# v1-psas-dev-board.net
KiCad netlist of a schematic drawn in EAGLE
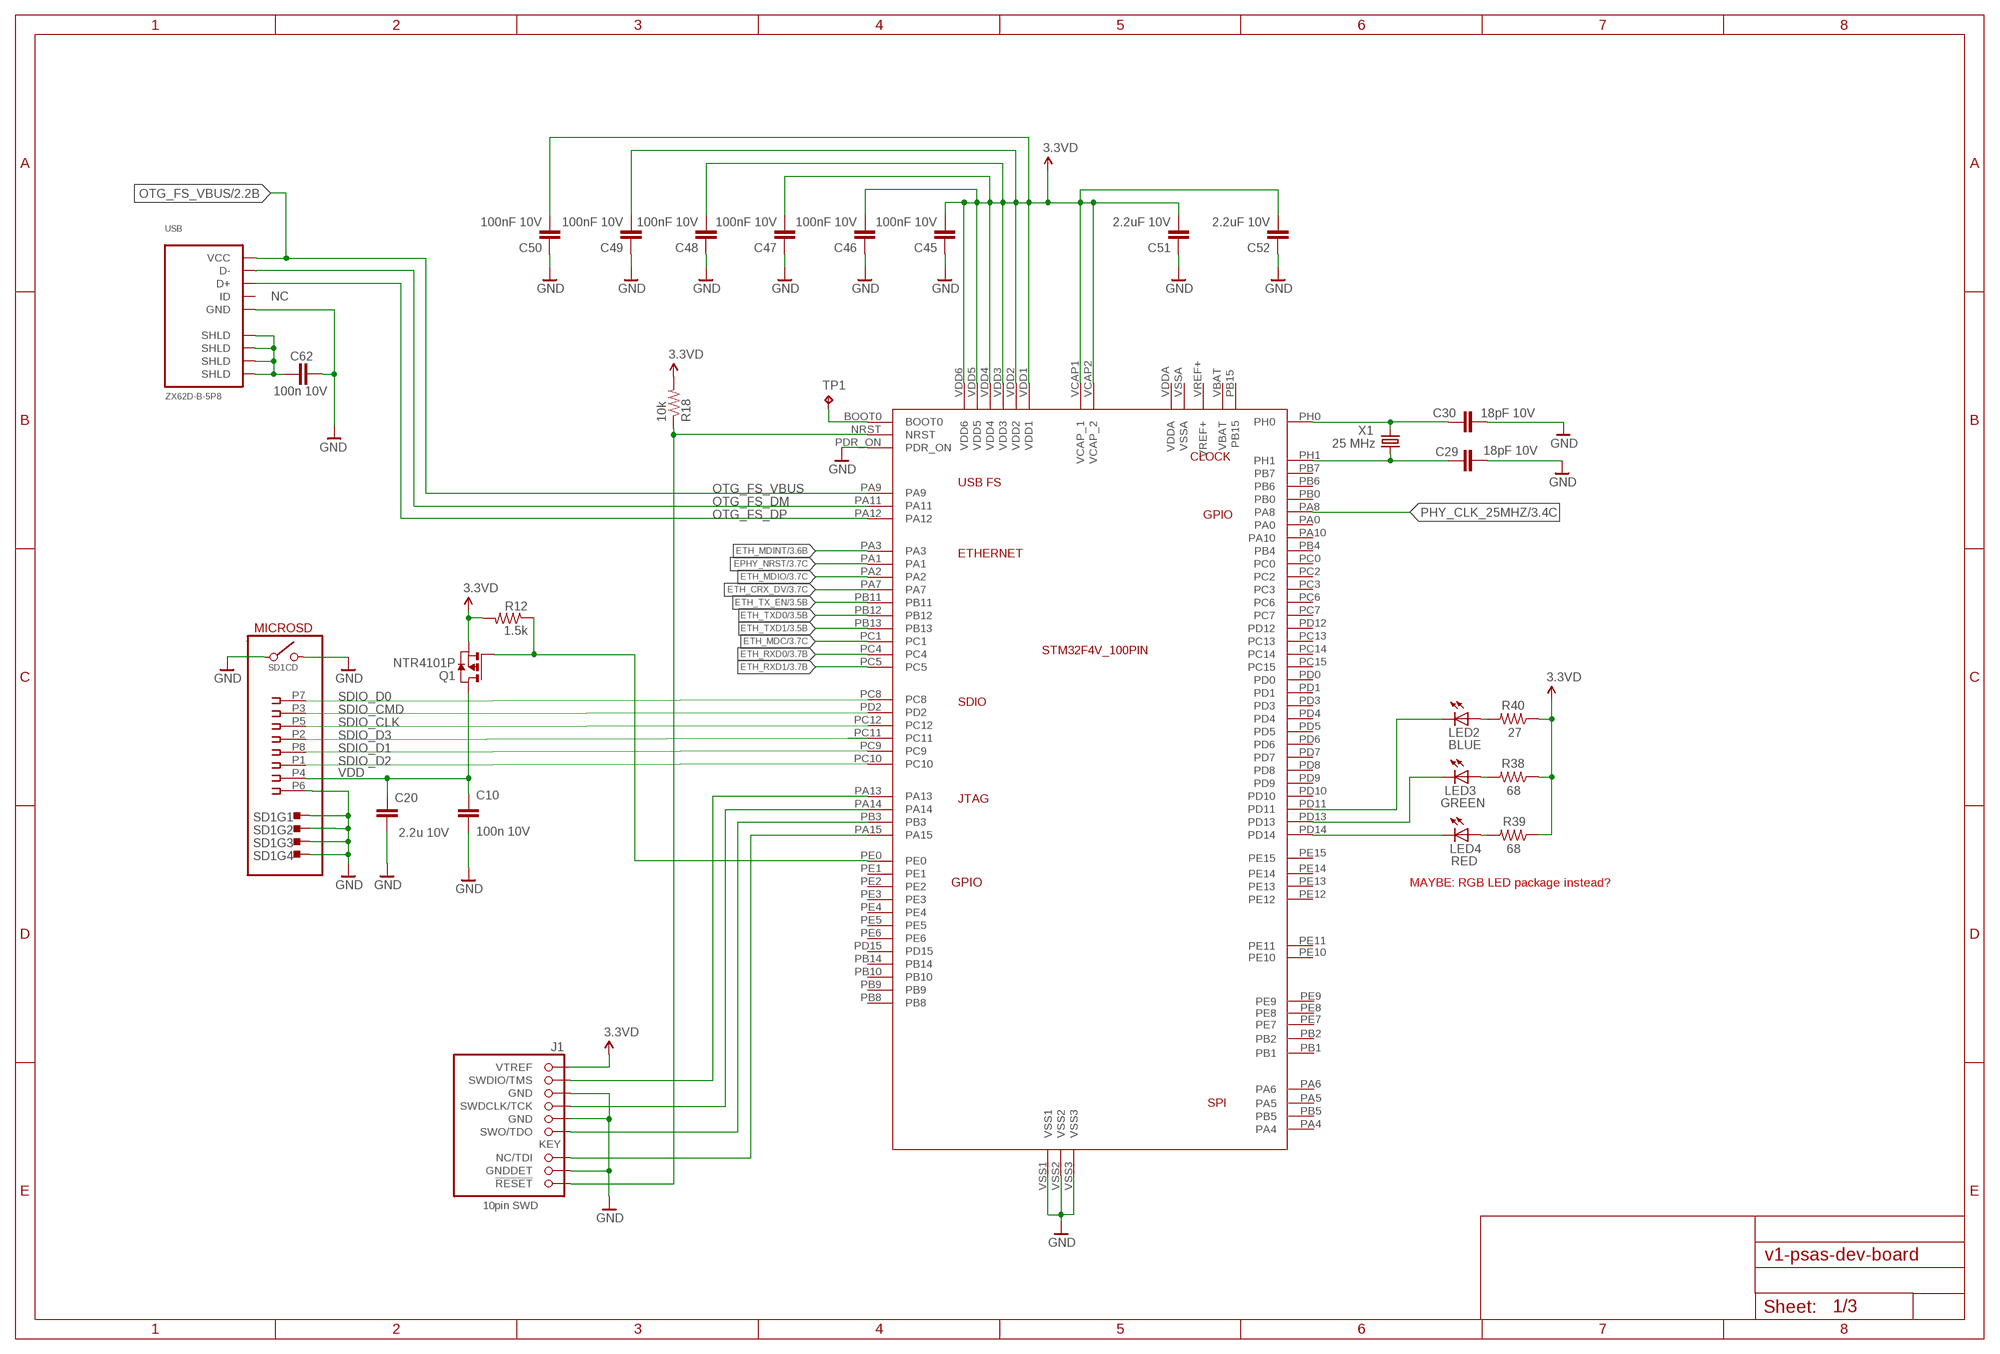
[diagram p0: schematic, sheet 1]
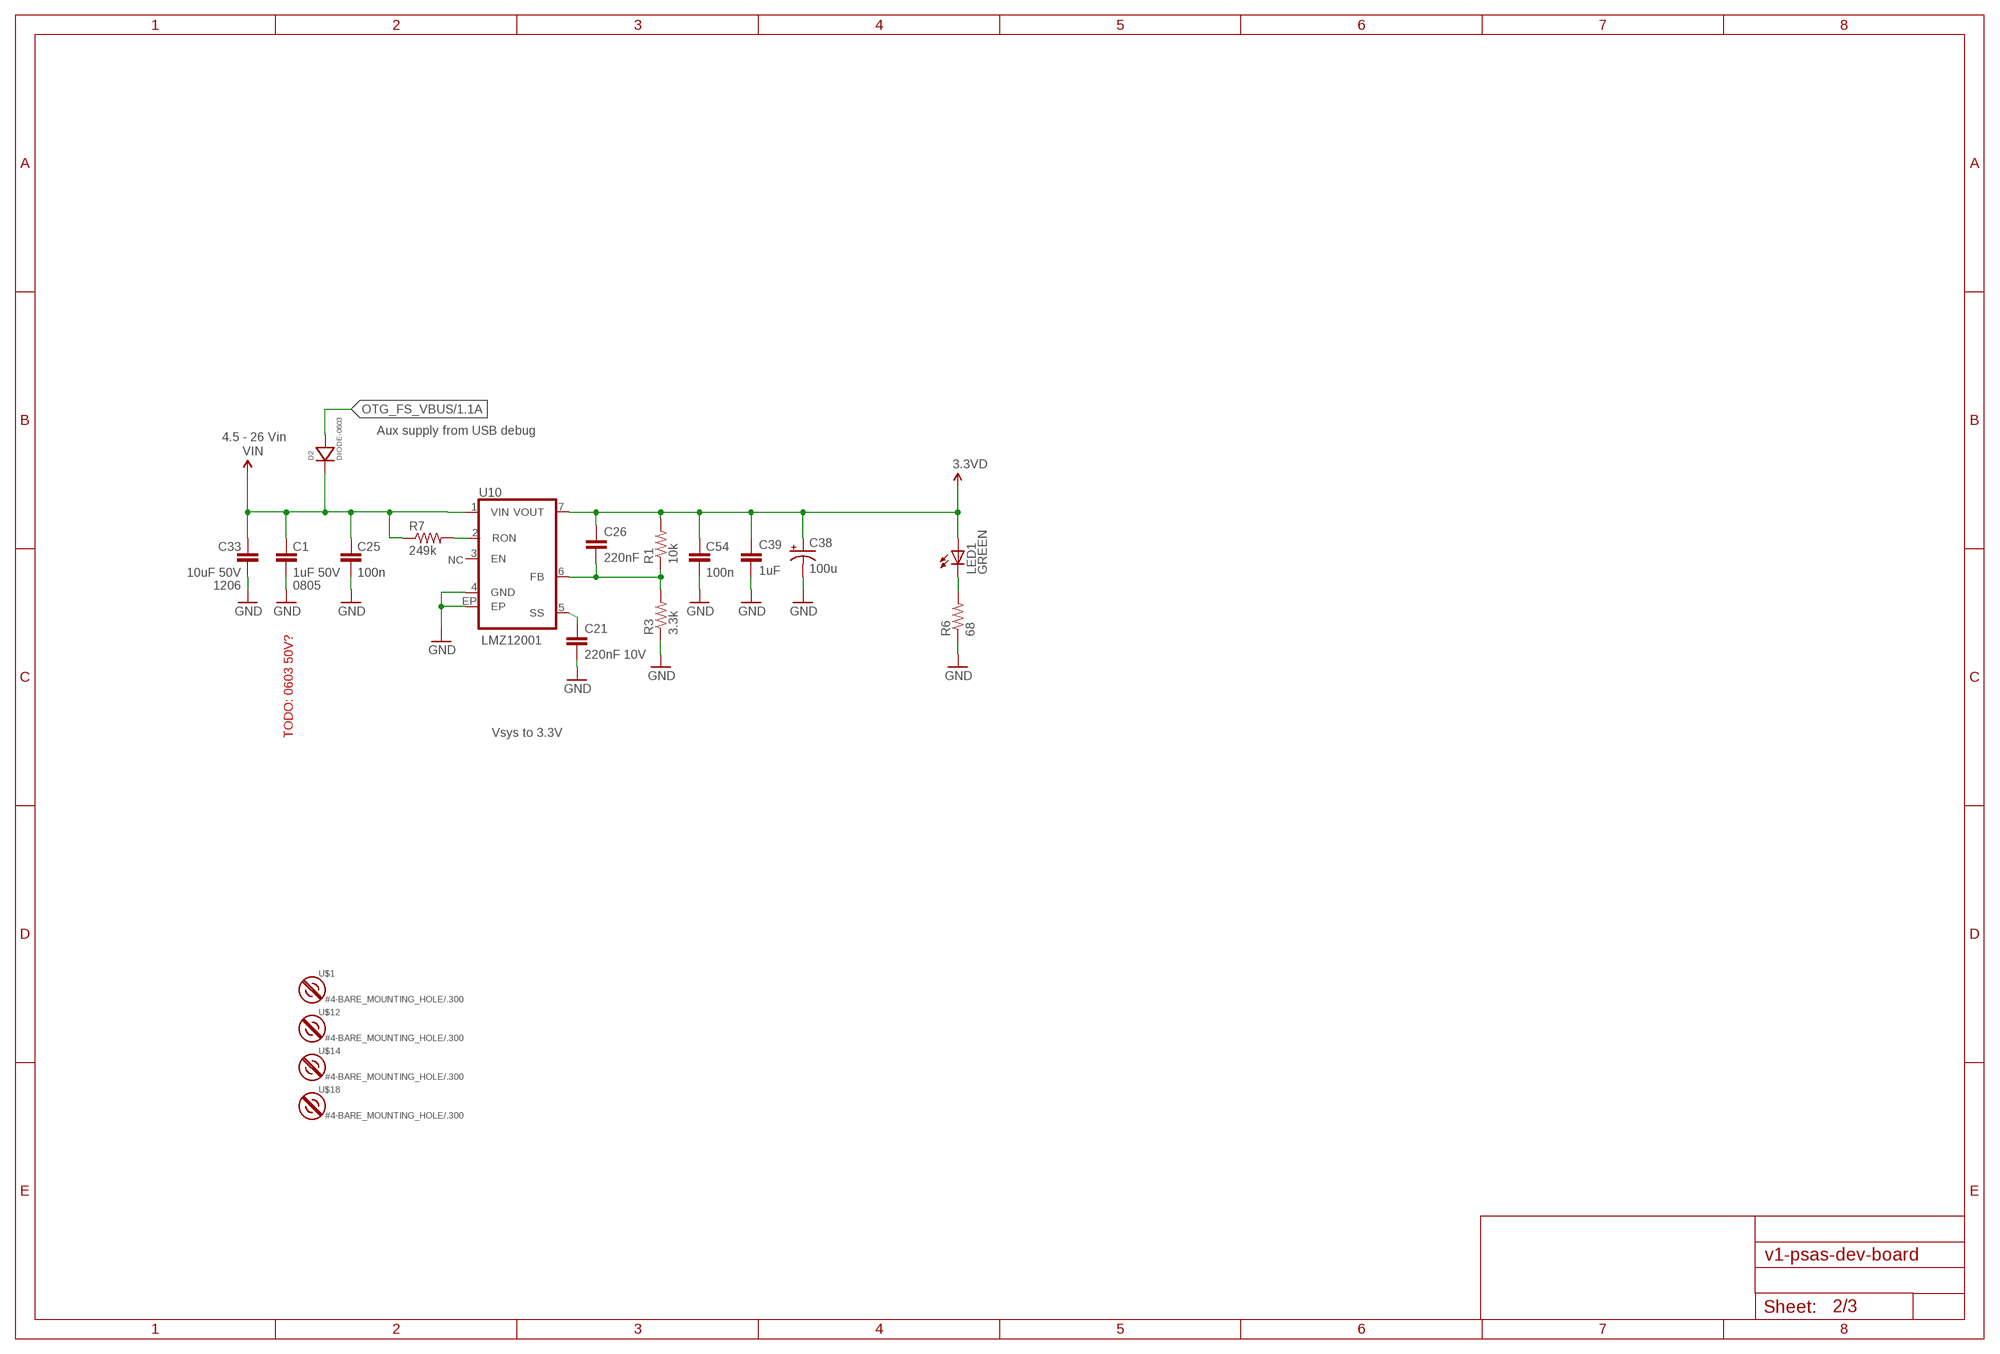
[diagram p1: schematic, sheet 2]
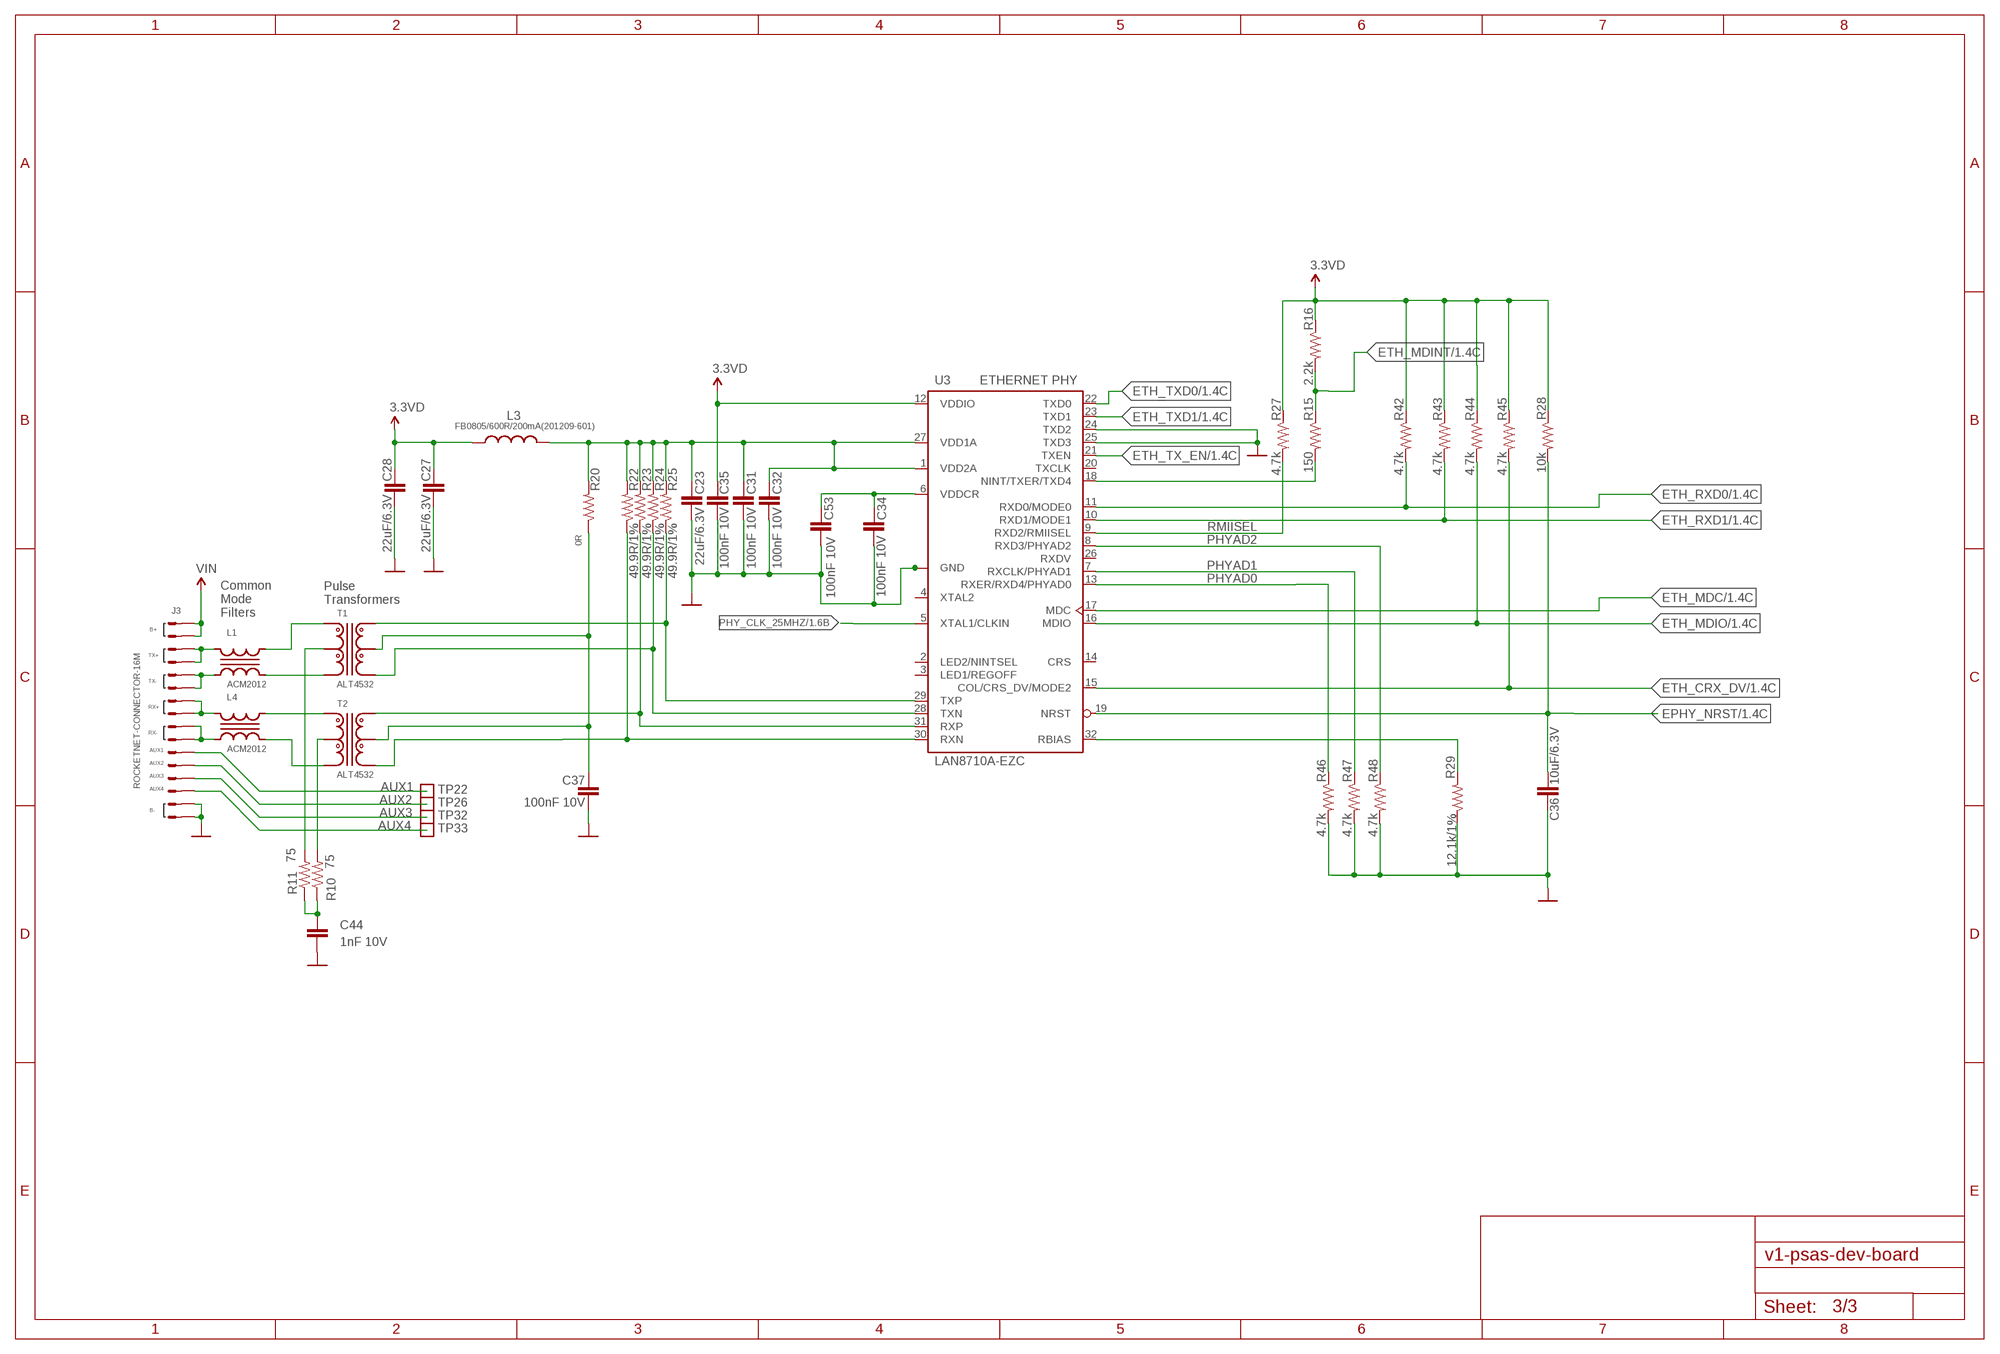
[diagram p2: schematic, sheet 3]

(export (version "E")
  (design (tool "Eeschema 10.0.6"))
  (components
    (comp (ref "C23")
      (value "22uF/6.3V")
      (footprint "eagle-import:1206-C")
      (libsource (lib "eagle-import") (part "C-EU1206-C"))
    )
    (comp (ref "C27")
      (value "22uF/6.3V")
      (footprint "eagle-import:1206-C")
      (libsource (lib "eagle-import") (part "C-EU1206-C"))
    )
    (comp (ref "C28")
      (value "22uF/6.3V")
      (footprint "eagle-import:1206-C")
      (libsource (lib "eagle-import") (part "C-EU1206-C"))
    )
    (comp (ref "C31")
      (value "100nF 10V")
      (footprint "eagle-import:0402-C-NOSILK")
      (libsource (lib "eagle-import") (part "C-EU0402-C-NOSILK"))
    )
    (comp (ref "C32")
      (value "100nF 10V")
      (footprint "eagle-import:0402-C-NOSILK")
      (libsource (lib "eagle-import") (part "C-EU0402-C-NOSILK"))
    )
    (comp (ref "C34")
      (value "100nF 10V")
      (footprint "eagle-import:0402-C-NOSILK")
      (libsource (lib "eagle-import") (part "C-EU0402-C-NOSILK"))
    )
    (comp (ref "C35")
      (value "100nF 10V")
      (footprint "eagle-import:0402-C-NOSILK")
      (libsource (lib "eagle-import") (part "C-EU0402-C-NOSILK"))
    )
    (comp (ref "C36")
      (value "10uF/6.3V")
      (footprint "eagle-import:1206-C")
      (libsource (lib "eagle-import") (part "C-EU1206-C"))
    )
    (comp (ref "C37")
      (value "100nF 10V")
      (footprint "eagle-import:0402-C-NOSILK")
      (libsource (lib "eagle-import") (part "C-EU0402-C-NOSILK"))
    )
    (comp (ref "C44")
      (value "1nF 10V")
      (footprint "eagle-import:0402-C-NOSILK")
      (libsource (lib "eagle-import") (part "C-EU0402-C-NOSILK"))
    )
    (comp (ref "C53")
      (value "100nF 10V")
      (footprint "eagle-import:0402-C-NOSILK")
      (libsource (lib "eagle-import") (part "C-EU0402-C-NOSILK"))
    )
    (comp (ref "J3")
      (value "ROCKETNET-CONNECTOR-16M")
      (footprint "eagle-import:ROCKETNET-M-16")
      (libsource (lib "eagle-import") (part "ROCKETNET-CONNECTOR-16M"))
    )
    (comp (ref "L1")
      (value "ACM2012")
      (footprint "eagle-import:TDK-ACM2012")
      (libsource (lib "eagle-import") (part "ACM2012"))
    )
    (comp (ref "L3")
      (value "FB0805/600R/200mA(201209-601)")
      (footprint "eagle-import:0805-C-NOSILK")
      (libsource (lib "eagle-import") (part "L-US0805-C-NOSILK"))
    )
    (comp (ref "L4")
      (value "ACM2012")
      (footprint "eagle-import:TDK-ACM2012")
      (libsource (lib "eagle-import") (part "ACM2012"))
    )
    (comp (ref "R10")
      (value "75")
      (footprint "eagle-import:0402-C-NOSILK")
      (libsource (lib "eagle-import") (part "R-US_0402-C-NOSILK"))
    )
    (comp (ref "R11")
      (value "75")
      (footprint "eagle-import:0402-C-NOSILK")
      (libsource (lib "eagle-import") (part "R-US_0402-C-NOSILK"))
    )
    (comp (ref "R15")
      (value "150")
      (footprint "eagle-import:0402-C-NOSILK")
      (libsource (lib "eagle-import") (part "R-US_0402-C-NOSILK"))
    )
    (comp (ref "R16")
      (value "2.2k")
      (footprint "eagle-import:0402-C-NOSILK")
      (libsource (lib "eagle-import") (part "R-US_0402-C-NOSILK"))
    )
    (comp (ref "R20")
      (value "0R")
      (footprint "eagle-import:0402-C-NOSILK")
      (libsource (lib "eagle-import") (part "R-US_0402-C-NOSILK"))
    )
    (comp (ref "R22")
      (value "49.9R/1%")
      (footprint "eagle-import:0402-C-NOSILK")
      (libsource (lib "eagle-import") (part "R-US_0402-C-NOSILK"))
    )
    (comp (ref "R23")
      (value "49.9R/1%")
      (footprint "eagle-import:0402-C-NOSILK")
      (libsource (lib "eagle-import") (part "R-US_0402-C-NOSILK"))
    )
    (comp (ref "R24")
      (value "49.9R/1%")
      (footprint "eagle-import:0402-C-NOSILK")
      (libsource (lib "eagle-import") (part "R-US_0402-C-NOSILK"))
    )
    (comp (ref "R25")
      (value "49.9R/1%")
      (footprint "eagle-import:0402-C-NOSILK")
      (libsource (lib "eagle-import") (part "R-US_0402-C-NOSILK"))
    )
    (comp (ref "R27")
      (value "4.7k")
      (footprint "eagle-import:0402-C-NOSILK")
      (libsource (lib "eagle-import") (part "R-US_0402-C-NOSILK"))
    )
    (comp (ref "R28")
      (value "10k")
      (footprint "eagle-import:0402-C-NOSILK")
      (libsource (lib "eagle-import") (part "R-US_0402-C-NOSILK"))
    )
    (comp (ref "R29")
      (value "12.1k/1%")
      (footprint "eagle-import:0402-C-NOSILK")
      (libsource (lib "eagle-import") (part "R-US_0402-C-NOSILK"))
    )
    (comp (ref "R42")
      (value "4.7k")
      (footprint "eagle-import:0402-C-NOSILK")
      (libsource (lib "eagle-import") (part "R-US_0402-C-NOSILK"))
    )
    (comp (ref "R43")
      (value "4.7k")
      (footprint "eagle-import:0402-C-NOSILK")
      (libsource (lib "eagle-import") (part "R-US_0402-C-NOSILK"))
    )
    (comp (ref "R44")
      (value "4.7k")
      (footprint "eagle-import:0402-C-NOSILK")
      (libsource (lib "eagle-import") (part "R-US_0402-C-NOSILK"))
    )
    (comp (ref "R45")
      (value "4.7k")
      (footprint "eagle-import:0402-C-NOSILK")
      (libsource (lib "eagle-import") (part "R-US_0402-C-NOSILK"))
    )
    (comp (ref "R46")
      (value "4.7k")
      (footprint "eagle-import:0402-C-NOSILK")
      (libsource (lib "eagle-import") (part "R-US_0402-C-NOSILK"))
    )
    (comp (ref "R47")
      (value "4.7k")
      (footprint "eagle-import:0402-C-NOSILK")
      (libsource (lib "eagle-import") (part "R-US_0402-C-NOSILK"))
    )
    (comp (ref "R48")
      (value "4.7k")
      (footprint "eagle-import:0402-C-NOSILK")
      (libsource (lib "eagle-import") (part "R-US_0402-C-NOSILK"))
    )
    (comp (ref "T1")
      (value "ALT4532")
      (footprint "eagle-import:TDK-ALT4532")
      (libsource (lib "eagle-import") (part "ALT4532"))
    )
    (comp (ref "T2")
      (value "ALT4532")
      (footprint "eagle-import:TDK-ALT4532")
      (libsource (lib "eagle-import") (part "ALT4532"))
    )
    (comp (ref "TP22")
      (value "TEST-POINT")
      (footprint "eagle-import:2MM-TEST-POINT")
      (libsource (lib "eagle-import") (part "TEST-POINT"))
    )
    (comp (ref "TP26")
      (value "TEST-POINT")
      (footprint "eagle-import:2MM-TEST-POINT")
      (libsource (lib "eagle-import") (part "TEST-POINT"))
    )
    (comp (ref "TP32")
      (value "TEST-POINT")
      (footprint "eagle-import:2MM-TEST-POINT")
      (libsource (lib "eagle-import") (part "TEST-POINT"))
    )
    (comp (ref "TP33")
      (value "TEST-POINT")
      (footprint "eagle-import:2MM-TEST-POINT")
      (libsource (lib "eagle-import") (part "TEST-POINT"))
    )
    (comp (ref "U3")
      (value "LAN8710A-EZC")
      (footprint "eagle-import:QFN-32(DRILLS)")
      (libsource (lib "eagle-import") (part "LAN8710A-EZC"))
    )
    (comp (ref "C10")
      (value "100n 10V")
      (footprint "eagle-import:0402-C-NOSILK")
      (libsource (lib "eagle-import") (part "C-EU0402-C-NOSILK"))
    )
    (comp (ref "C20")
      (value "2.2u 10V")
      (footprint "eagle-import:0603-C-NOSILK")
      (libsource (lib "eagle-import") (part "C-EU0603-C-NOSILK"))
    )
    (comp (ref "C29")
      (value "18pF 10V")
      (footprint "eagle-import:0402-C-NOSILK")
      (libsource (lib "eagle-import") (part "C-EU0402-C-NOSILK"))
    )
    (comp (ref "C30")
      (value "18pF 10V")
      (footprint "eagle-import:0402-C-NOSILK")
      (libsource (lib "eagle-import") (part "C-EU0402-C-NOSILK"))
    )
    (comp (ref "C45")
      (value "100nF 10V")
      (footprint "eagle-import:0402-C-NOSILK")
      (libsource (lib "eagle-import") (part "C-EU0402-C-NOSILK"))
    )
    (comp (ref "C46")
      (value "100nF 10V")
      (footprint "eagle-import:0402-C-NOSILK")
      (libsource (lib "eagle-import") (part "C-EU0402-C-NOSILK"))
    )
    (comp (ref "C47")
      (value "100nF 10V")
      (footprint "eagle-import:0402-C-NOSILK")
      (libsource (lib "eagle-import") (part "C-EU0402-C-NOSILK"))
    )
    (comp (ref "C48")
      (value "100nF 10V")
      (footprint "eagle-import:0402-C-NOSILK")
      (libsource (lib "eagle-import") (part "C-EU0402-C-NOSILK"))
    )
    (comp (ref "C49")
      (value "100nF 10V")
      (footprint "eagle-import:0402-C-NOSILK")
      (libsource (lib "eagle-import") (part "C-EU0402-C-NOSILK"))
    )
    (comp (ref "C50")
      (value "100nF 10V")
      (footprint "eagle-import:0402-C-NOSILK")
      (libsource (lib "eagle-import") (part "C-EU0402-C-NOSILK"))
    )
    (comp (ref "C51")
      (value "2.2uF 10V")
      (footprint "eagle-import:0603-C-NOSILK")
      (libsource (lib "eagle-import") (part "C-EU0603-C-NOSILK"))
    )
    (comp (ref "C52")
      (value "2.2uF 10V")
      (footprint "eagle-import:0603-C-NOSILK")
      (libsource (lib "eagle-import") (part "C-EU0603-C-NOSILK"))
    )
    (comp (ref "C62")
      (value "100n 10V")
      (footprint "eagle-import:0402-C-NOSILK")
      (libsource (lib "eagle-import") (part "C-EU0402-C-NOSILK"))
    )
    (comp (ref "J1")
      (value "1.27MM-SWD-CONNECTOR")
      (footprint "eagle-import:1.27MM_2X5")
      (libsource (lib "eagle-import") (part "1.27MM-SWD-CONNECTOR"))
    )
    (comp (ref "LED2")
      (value "BLUE")
      (footprint "eagle-import:CHIP-LED0603")
      (libsource (lib "eagle-import") (part "LEDCHIP-LED0603"))
    )
    (comp (ref "LED3")
      (value "GREEN")
      (footprint "eagle-import:CHIP-LED0603")
      (libsource (lib "eagle-import") (part "LEDCHIP-LED0603"))
    )
    (comp (ref "LED4")
      (value "RED")
      (footprint "eagle-import:CHIP-LED0603")
      (libsource (lib "eagle-import") (part "LEDCHIP-LED0603"))
    )
    (comp (ref "Q1")
      (value "NTR4101P")
      (footprint "eagle-import:SOT23")
      (libsource (lib "eagle-import") (part "NTR4101P"))
    )
    (comp (ref "R12")
      (value "1.5k")
      (footprint "eagle-import:0402-C-NOSILK")
      (libsource (lib "eagle-import") (part "R-US_0402-C-NOSILK"))
    )
    (comp (ref "R18")
      (value "10k")
      (footprint "eagle-import:0402-C-NOSILK")
      (libsource (lib "eagle-import") (part "R-US_0402-C-NOSILK"))
    )
    (comp (ref "R38")
      (value "68")
      (footprint "eagle-import:0402-C-NOSILK")
      (libsource (lib "eagle-import") (part "R-US_0402-C-NOSILK"))
    )
    (comp (ref "R39")
      (value "68")
      (footprint "eagle-import:0402-C-NOSILK")
      (libsource (lib "eagle-import") (part "R-US_0402-C-NOSILK"))
    )
    (comp (ref "R40")
      (value "27")
      (footprint "eagle-import:0402-C-NOSILK")
      (libsource (lib "eagle-import") (part "R-US_0402-C-NOSILK"))
    )
    (comp (ref "SD1")
      (value "CON_HIROSE_DM3D(MICROSD)")
      (footprint "eagle-import:HIROSE_DM3D(MICRO-SD)")
      (libsource (lib "eagle-import") (part "CON_HIROSE_DM3D(MICROSD)"))
    )
    (comp (ref "TP1")
      (value "TPTP06R")
      (footprint "eagle-import:TP06R")
      (libsource (lib "eagle-import") (part "TPTP06R"))
    )
    (comp (ref "U8")
      (value "STM32F4V")
      (footprint "eagle-import:LQFP100")
      (libsource (lib "eagle-import") (part "STM32F4V_100PIN_GPSBOARD"))
    )
    (comp (ref "USB")
      (value "ZX62D-B-5P8")
      (footprint "eagle-import:ZX62D-B-5P8")
      (libsource (lib "eagle-import") (part "ZX62D-B-5P8"))
    )
    (comp (ref "X1")
      (value "25 MHz")
      (footprint "eagle-import:CTS406")
      (libsource (lib "eagle-import") (part "CRYSTALCTS406"))
    )
    (comp (ref "C1")
      (value "1uF 50V")
      (footprint "eagle-import:0805-B-NOSILK")
      (libsource (lib "eagle-import") (part "C-EU0805-B-NOSILK"))
    )
    (comp (ref "C21")
      (value "220nF 10V")
      (footprint "eagle-import:0402-C-NOSILK")
      (libsource (lib "eagle-import") (part "C-EU0402-C-NOSILK"))
    )
    (comp (ref "C25")
      (value "100n")
      (footprint "eagle-import:0402-B-NOSILK")
      (libsource (lib "eagle-import") (part "C-EU0402-B-NOSILK"))
    )
    (comp (ref "C26")
      (value "220nF")
      (footprint "eagle-import:0402-C-NOSILK")
      (libsource (lib "eagle-import") (part "C-EU0402-C-NOSILK"))
    )
    (comp (ref "C33")
      (value "10uF 50V")
      (footprint "eagle-import:1206-C")
      (libsource (lib "eagle-import") (part "C-EU1206-C"))
    )
    (comp (ref "C38")
      (value "100u")
      (footprint "eagle-import:EIA6032")
      (libsource (lib "eagle-import") (part "CAP_POL6032"))
    )
    (comp (ref "C39")
      (value "1uF")
      (footprint "eagle-import:0603-B-NOSILK")
      (libsource (lib "eagle-import") (part "C-EU0603-B-NOSILK"))
    )
    (comp (ref "C54")
      (value "100n")
      (footprint "eagle-import:0402-B-NOSILK")
      (libsource (lib "eagle-import") (part "C-EU0402-B-NOSILK"))
    )
    (comp (ref "D2")
      (value "DIODE-0603")
      (footprint "eagle-import:0603-B-NOSILK-DIODE")
      (libsource (lib "eagle-import") (part "DIODE-0603"))
    )
    (comp (ref "LED1")
      (value "GREEN")
      (footprint "eagle-import:CHIP-LED0603")
      (libsource (lib "eagle-import") (part "LEDCHIP-LED0603"))
    )
    (comp (ref "R1")
      (value "10k")
      (footprint "eagle-import:0402-C-NOSILK")
      (libsource (lib "eagle-import") (part "R-US_0402-C-NOSILK"))
    )
    (comp (ref "R3")
      (value "3.3k")
      (footprint "eagle-import:0402-C-NOSILK")
      (libsource (lib "eagle-import") (part "R-US_0402-C-NOSILK"))
    )
    (comp (ref "R6")
      (value "68")
      (footprint "eagle-import:0402-C-NOSILK")
      (libsource (lib "eagle-import") (part "R-US_0402-C-NOSILK"))
    )
    (comp (ref "R7")
      (value "249k")
      (footprint "eagle-import:0402-C-NOSILK")
      (libsource (lib "eagle-import") (part "R-US_0402-C-NOSILK"))
    )
    (comp (ref "U$1")
      (value "#4-BARE_MOUNTING_HOLE/.300")
      (footprint "eagle-import:#4_.300-BARE+STD_NUT_OR_STAR_WASHER")
      (libsource (lib "eagle-import") (part "#4-BARE_MOUNTING_HOLE/.300"))
    )
    (comp (ref "U$12")
      (value "#4-BARE_MOUNTING_HOLE/.300")
      (footprint "eagle-import:#4_.300-BARE+STD_NUT_OR_STAR_WASHER")
      (libsource (lib "eagle-import") (part "#4-BARE_MOUNTING_HOLE/.300"))
    )
    (comp (ref "U$14")
      (value "#4-BARE_MOUNTING_HOLE/.300")
      (footprint "eagle-import:#4_.300-BARE+STD_NUT_OR_STAR_WASHER")
      (libsource (lib "eagle-import") (part "#4-BARE_MOUNTING_HOLE/.300"))
    )
    (comp (ref "U$18")
      (value "#4-BARE_MOUNTING_HOLE/.300")
      (footprint "eagle-import:#4_.300-BARE+STD_NUT_OR_STAR_WASHER")
      (libsource (lib "eagle-import") (part "#4-BARE_MOUNTING_HOLE/.300"))
    )
    (comp (ref "U10")
      (value "LMZ12001")
      (footprint "eagle-import:TO-PMOD-7")
      (libsource (lib "eagle-import") (part "LMZ12001"))
    )
  )
  (nets
    (net (code "1") (name "3.3VD") (class "Default")
      (node (ref "C26") (pin "1") (pinfunction "1_1") (pintype "passive"))
      (node (ref "C27") (pin "2") (pinfunction "2_2") (pintype "passive"))
      (node (ref "C28") (pin "2") (pinfunction "2_2") (pintype "passive"))
      (node (ref "C35") (pin "1") (pinfunction "1_1") (pintype "passive"))
      (node (ref "C38") (pin "P$1") (pinfunction "+_P$1") (pintype "passive"))
      (node (ref "C39") (pin "1") (pinfunction "1_1") (pintype "passive"))
      (node (ref "C45") (pin "2") (pinfunction "2_2") (pintype "passive"))
      (node (ref "C46") (pin "2") (pinfunction "2_2") (pintype "passive"))
      (node (ref "C47") (pin "2") (pinfunction "2_2") (pintype "passive"))
      (node (ref "C48") (pin "2") (pinfunction "2_2") (pintype "passive"))
      (node (ref "C49") (pin "2") (pinfunction "2_2") (pintype "passive"))
      (node (ref "C50") (pin "2") (pinfunction "2_2") (pintype "passive"))
      (node (ref "C51") (pin "2") (pinfunction "2_2") (pintype "passive"))
      (node (ref "C52") (pin "2") (pinfunction "2_2") (pintype "passive"))
      (node (ref "C54") (pin "1") (pinfunction "1_1") (pintype "passive"))
      (node (ref "J1") (pin "VTREF") (pinfunction "VTREF_VTREF") (pintype "passive"))
      (node (ref "L3") (pin "2") (pinfunction "2_2") (pintype "passive"))
      (node (ref "LED1") (pin "A") (pinfunction "A_A") (pintype "passive"))
      (node (ref "Q1") (pin "2") (pinfunction "S_2") (pintype "passive"))
      (node (ref "R1") (pin "2") (pinfunction "2_2") (pintype "passive"))
      (node (ref "R12") (pin "2") (pinfunction "2_2") (pintype "passive"))
      (node (ref "R16") (pin "1") (pinfunction "1_1") (pintype "passive"))
      (node (ref "R18") (pin "2") (pinfunction "2_2") (pintype "passive"))
      (node (ref "R27") (pin "1") (pinfunction "1_1") (pintype "passive"))
      (node (ref "R28") (pin "1") (pinfunction "1_1") (pintype "passive"))
      (node (ref "R38") (pin "1") (pinfunction "1_1") (pintype "passive"))
      (node (ref "R39") (pin "1") (pinfunction "1_1") (pintype "passive"))
      (node (ref "R40") (pin "1") (pinfunction "1_1") (pintype "passive"))
      (node (ref "R42") (pin "1") (pinfunction "1_1") (pintype "passive"))
      (node (ref "R43") (pin "1") (pinfunction "1_1") (pintype "passive"))
      (node (ref "R44") (pin "1") (pinfunction "1_1") (pintype "passive"))
      (node (ref "R45") (pin "1") (pinfunction "1_1") (pintype "passive"))
      (node (ref "U10") (pin "7") (pinfunction "VOUT_7") (pintype "bidirectional"))
      (node (ref "U3") (pin "12") (pinfunction "VDDIO_12") (pintype "power_in"))
      (node (ref "U8") (pin "VCAP1") (pinfunction "VCAP_1_VCAP1") (pintype "bidirectional"))
      (node (ref "U8") (pin "VCAP2") (pinfunction "VCAP_2_VCAP2") (pintype "bidirectional"))
      (node (ref "U8") (pin "VDD1") (pinfunction "VDD1_VDD1") (pintype "power_in"))
      (node (ref "U8") (pin "VDD2") (pinfunction "VDD2_VDD2") (pintype "power_in"))
      (node (ref "U8") (pin "VDD3") (pinfunction "VDD3_VDD3") (pintype "power_in"))
      (node (ref "U8") (pin "VDD4") (pinfunction "VDD4_VDD4") (pintype "power_in"))
      (node (ref "U8") (pin "VDD5") (pinfunction "VDD5_VDD5") (pintype "power_in"))
      (node (ref "U8") (pin "VDD6") (pinfunction "VDD6_VDD6") (pintype "power_in"))
    )
    (net (code "2") (name "AUX1") (class "Default")
      (node (ref "J3") (pin "A1") (pinfunction "AUX1_A1") (pintype "passive"))
      (node (ref "TP22") (pin "1") (pinfunction "1_1") (pintype "passive"))
    )
    (net (code "3") (name "AUX2") (class "Default")
      (node (ref "J3") (pin "A2") (pinfunction "AUX2_A2") (pintype "passive"))
      (node (ref "TP26") (pin "1") (pinfunction "1_1") (pintype "passive"))
    )
    (net (code "4") (name "AUX3") (class "Default")
      (node (ref "J3") (pin "A3") (pinfunction "AUX3_A3") (pintype "passive"))
      (node (ref "TP32") (pin "1") (pinfunction "1_1") (pintype "passive"))
    )
    (net (code "5") (name "AUX4") (class "Default")
      (node (ref "J3") (pin "A4") (pinfunction "AUX4_A4") (pintype "passive"))
      (node (ref "TP33") (pin "1") (pinfunction "1_1") (pintype "passive"))
    )
    (net (code "6") (name "EPHY_NRST") (class "Default")
      (node (ref "C36") (pin "2") (pinfunction "2_2") (pintype "passive"))
      (node (ref "R28") (pin "2") (pinfunction "2_2") (pintype "passive"))
      (node (ref "U3") (pin "19") (pinfunction "NRST_19") (pintype "input"))
      (node (ref "U8") (pin "PA1") (pinfunction "PA1_PA1") (pintype "bidirectional"))
    )
    (net (code "7") (name "ETH_CRX_DV") (class "Default")
      (node (ref "R45") (pin "2") (pinfunction "2_2") (pintype "passive"))
      (node (ref "U3") (pin "15") (pinfunction "COL/CRS_DV/MODE2_15") (pintype "bidirectional"))
      (node (ref "U8") (pin "PA7") (pinfunction "PA7_PA7") (pintype "bidirectional"))
    )
    (net (code "8") (name "ETH_MDC") (class "Default")
      (node (ref "U3") (pin "17") (pinfunction "MDC_17") (pintype "input"))
      (node (ref "U8") (pin "PC1") (pinfunction "PC1_PC1") (pintype "bidirectional"))
    )
    (net (code "9") (name "ETH_MDINT") (class "Default")
      (node (ref "R15") (pin "1") (pinfunction "1_1") (pintype "passive"))
      (node (ref "R16") (pin "2") (pinfunction "2_2") (pintype "passive"))
      (node (ref "U8") (pin "PA3") (pinfunction "PA3_PA3") (pintype "bidirectional"))
    )
    (net (code "10") (name "ETH_MDIO") (class "Default")
      (node (ref "R44") (pin "2") (pinfunction "2_2") (pintype "passive"))
      (node (ref "U3") (pin "16") (pinfunction "MDIO_16") (pintype "bidirectional"))
      (node (ref "U8") (pin "PA2") (pinfunction "PA2_PA2") (pintype "bidirectional"))
    )
    (net (code "11") (name "ETH_RXD0") (class "Default")
      (node (ref "R42") (pin "2") (pinfunction "2_2") (pintype "passive"))
      (node (ref "U3") (pin "11") (pinfunction "RXD0/MODE0_11") (pintype "bidirectional"))
      (node (ref "U8") (pin "PC4") (pinfunction "PC4_PC4") (pintype "bidirectional"))
    )
    (net (code "12") (name "ETH_RXD1") (class "Default")
      (node (ref "R43") (pin "2") (pinfunction "2_2") (pintype "passive"))
      (node (ref "U3") (pin "10") (pinfunction "RXD1/MODE1_10") (pintype "bidirectional"))
      (node (ref "U8") (pin "PC5") (pinfunction "PC5_PC5") (pintype "bidirectional"))
    )
    (net (code "13") (name "ETH_TXD0") (class "Default")
      (node (ref "U3") (pin "22") (pinfunction "TXD0_22") (pintype "input"))
      (node (ref "U8") (pin "PB12") (pinfunction "PB12_PB12") (pintype "bidirectional"))
    )
    (net (code "14") (name "ETH_TXD1") (class "Default")
      (node (ref "U3") (pin "23") (pinfunction "TXD1_23") (pintype "input"))
      (node (ref "U8") (pin "PB13") (pinfunction "PB13_PB13") (pintype "bidirectional"))
    )
    (net (code "15") (name "ETH_TX_EN") (class "Default")
      (node (ref "U3") (pin "21") (pinfunction "TXEN_21") (pintype "input"))
      (node (ref "U8") (pin "PB11") (pinfunction "PB11_PB11") (pintype "bidirectional"))
    )
    (net (code "16") (name "GND") (class "Default")
      (node (ref "C1") (pin "2") (pinfunction "2_2") (pintype "passive"))
      (node (ref "C10") (pin "1") (pinfunction "1_1") (pintype "passive"))
      (node (ref "C20") (pin "1") (pinfunction "1_1") (pintype "passive"))
      (node (ref "C21") (pin "2") (pinfunction "2_2") (pintype "passive"))
      (node (ref "C23") (pin "1") (pinfunction "1_1") (pintype "passive"))
      (node (ref "C25") (pin "2") (pinfunction "2_2") (pintype "passive"))
      (node (ref "C27") (pin "1") (pinfunction "1_1") (pintype "passive"))
      (node (ref "C28") (pin "1") (pinfunction "1_1") (pintype "passive"))
      (node (ref "C29") (pin "1") (pinfunction "1_1") (pintype "passive"))
      (node (ref "C30") (pin "1") (pinfunction "1_1") (pintype "passive"))
      (node (ref "C31") (pin "1") (pinfunction "1_1") (pintype "passive"))
      (node (ref "C32") (pin "1") (pinfunction "1_1") (pintype "passive"))
      (node (ref "C33") (pin "2") (pinfunction "2_2") (pintype "passive"))
      (node (ref "C34") (pin "1") (pinfunction "1_1") (pintype "passive"))
      (node (ref "C35") (pin "2") (pinfunction "2_2") (pintype "passive"))
      (node (ref "C36") (pin "1") (pinfunction "1_1") (pintype "passive"))
      (node (ref "C37") (pin "1") (pinfunction "1_1") (pintype "passive"))
      (node (ref "C38") (pin "P$2") (pinfunction "-_P$2") (pintype "passive"))
      (node (ref "C39") (pin "2") (pinfunction "2_2") (pintype "passive"))
      (node (ref "C44") (pin "1") (pinfunction "1_1") (pintype "passive"))
      (node (ref "C45") (pin "1") (pinfunction "1_1") (pintype "passive"))
      (node (ref "C46") (pin "1") (pinfunction "1_1") (pintype "passive"))
      (node (ref "C47") (pin "1") (pinfunction "1_1") (pintype "passive"))
      (node (ref "C48") (pin "1") (pinfunction "1_1") (pintype "passive"))
      (node (ref "C49") (pin "1") (pinfunction "1_1") (pintype "passive"))
      (node (ref "C50") (pin "1") (pinfunction "1_1") (pintype "passive"))
      (node (ref "C51") (pin "1") (pinfunction "1_1") (pintype "passive"))
      (node (ref "C52") (pin "1") (pinfunction "1_1") (pintype "passive"))
      (node (ref "C53") (pin "1") (pinfunction "1_1") (pintype "passive"))
      (node (ref "C54") (pin "2") (pinfunction "2_2") (pintype "passive"))
      (node (ref "C62") (pin "1") (pinfunction "1_1") (pintype "passive"))
      (node (ref "J1") (pin "GND") (pinfunction "GND_GND") (pintype "passive"))
      (node (ref "J1") (pin "GND@2") (pinfunction "GND_GND@2") (pintype "passive"))
      (node (ref "J1") (pin "GNDDET") (pinfunction "GNDDET_GNDDET") (pintype "passive"))
      (node (ref "J3") (pin "B-@1") (pinfunction "B-_B-@1") (pintype "power_in"))
      (node (ref "J3") (pin "B-@2") (pinfunction "B-_B-@2") (pintype "power_in"))
      (node (ref "R29") (pin "1") (pinfunction "1_1") (pintype "passive"))
      (node (ref "R3") (pin "1") (pinfunction "1_1") (pintype "passive"))
      (node (ref "R46") (pin "2") (pinfunction "2_2") (pintype "passive"))
      (node (ref "R47") (pin "2") (pinfunction "2_2") (pintype "passive"))
      (node (ref "R48") (pin "2") (pinfunction "2_2") (pintype "passive"))
      (node (ref "R6") (pin "1") (pinfunction "1_1") (pintype "passive"))
      (node (ref "SD1") (pin "G1") (pinfunction "PAD_G1") (pintype "passive"))
      (node (ref "SD1") (pin "G2") (pinfunction "PAD_G2") (pintype "passive"))
      (node (ref "SD1") (pin "G3") (pinfunction "PAD_G3") (pintype "passive"))
      (node (ref "SD1") (pin "G4") (pinfunction "PAD_G4") (pintype "passive"))
      (node (ref "SD1") (pin "P6") (pinfunction "6_P6") (pintype "passive"))
      (node (ref "SD1") (pin "S0") (pinfunction "0_S0") (pintype "passive"))
      (node (ref "SD1") (pin "S1") (pinfunction "1_S1") (pintype "passive"))
      (node (ref "U10") (pin "4") (pinfunction "GND_4") (pintype "bidirectional"))
      (node (ref "U10") (pin "EP") (pinfunction "EP_EP") (pintype "bidirectional"))
      (node (ref "U3") (pin "24") (pinfunction "TXD2_24") (pintype "input"))
      (node (ref "U3") (pin "25") (pinfunction "TXD3_25") (pintype "input"))
      (node (ref "U3") (pin "GND") (pinfunction "GND_GND") (pintype "power_in"))
      (node (ref "U8") (pin "PDR_ON") (pinfunction "PDR_ON_PDR_ON") (pintype "bidirectional"))
      (node (ref "U8") (pin "VSS1") (pinfunction "VSS1_VSS1") (pintype "power_in"))
      (node (ref "U8") (pin "VSS2") (pinfunction "VSS2_VSS2") (pintype "power_in"))
      (node (ref "U8") (pin "VSS3") (pinfunction "VSS3_VSS3") (pintype "power_in"))
      (node (ref "USB") (pin "P5") (pinfunction "GND_P5") (pintype "power_in"))
    )
    (net (code "17") (name "Net-(C29-Pad2)") (class "Default")
      (node (ref "C29") (pin "2") (pinfunction "2_2") (pintype "passive"))
      (node (ref "U8") (pin "PH1") (pinfunction "PH1_PH1") (pintype "bidirectional"))
      (node (ref "X1") (pin "1") (pinfunction "1_1") (pintype "passive"))
    )
    (net (code "18") (name "Net-(C37-Pad2)") (class "Default")
      (node (ref "C37") (pin "2") (pinfunction "2_2") (pintype "passive"))
      (node (ref "R20") (pin "1") (pinfunction "1_1") (pintype "passive"))
      (node (ref "T1") (pin "3") (pinfunction "3_3") (pintype "passive"))
      (node (ref "T2") (pin "3") (pinfunction "3_3") (pintype "passive"))
    )
    (net (code "19") (name "Net-(C44-Pad2)") (class "Default")
      (node (ref "C44") (pin "2") (pinfunction "2_2") (pintype "passive"))
      (node (ref "R10") (pin "1") (pinfunction "1_1") (pintype "passive"))
      (node (ref "R11") (pin "1") (pinfunction "1_1") (pintype "passive"))
    )
    (net (code "20") (name "Net-(C62-Pad2)") (class "Default")
      (node (ref "C62") (pin "2") (pinfunction "2_2") (pintype "passive"))
      (node (ref "USB") (pin "P$1") (pinfunction "SHLD_P$1") (pintype "power_in"))
      (node (ref "USB") (pin "P$2") (pinfunction "SHLD_P$2") (pintype "power_in"))
      (node (ref "USB") (pin "P$3") (pinfunction "SHLD_P$3") (pintype "power_in"))
      (node (ref "USB") (pin "P$4") (pinfunction "SHLD_P$4") (pintype "power_in"))
    )
    (net (code "21") (name "Net-(J1-NC{slash}TDI)") (class "Default")
      (node (ref "J1") (pin "NC") (pinfunction "NC/TDI_NC") (pintype "passive"))
      (node (ref "U8") (pin "PA15") (pinfunction "PA15_PA15") (pintype "bidirectional"))
    )
    (net (code "22") (name "Net-(J1-SWDCLK{slash}TCK)") (class "Default")
      (node (ref "J1") (pin "SWDCLK") (pinfunction "SWDCLK/TCK_SWDCLK") (pintype "passive"))
      (node (ref "U8") (pin "PA14") (pinfunction "PA14_PA14") (pintype "bidirectional"))
    )
    (net (code "23") (name "Net-(J1-SWDIO{slash}TMS)") (class "Default")
      (node (ref "J1") (pin "SWDIO") (pinfunction "SWDIO/TMS_SWDIO") (pintype "passive"))
      (node (ref "U8") (pin "PA13") (pinfunction "PA13_PA13") (pintype "bidirectional"))
    )
    (net (code "24") (name "Net-(J1-SWO{slash}TDO)") (class "Default")
      (node (ref "J1") (pin "SWO") (pinfunction "SWO/TDO_SWO") (pintype "passive"))
      (node (ref "U8") (pin "PB3") (pinfunction "PB3_PB3") (pintype "bidirectional"))
    )
    (net (code "25") (name "Net-(J1-~{RESET})") (class "Default")
      (node (ref "J1") (pin "!RESET") (pinfunction "~{RESET}_!RESET") (pintype "passive"))
      (node (ref "R18") (pin "1") (pinfunction "1_1") (pintype "passive"))
      (node (ref "U8") (pin "NRST") (pinfunction "NRST_NRST") (pintype "bidirectional"))
    )
    (net (code "26") (name "Net-(J3-RX+-PadR+@5)") (class "Default")
      (node (ref "J3") (pin "R+@5") (pinfunction "RX+_R+@5") (pintype "passive"))
      (node (ref "J3") (pin "R+@7") (pinfunction "RX+_R+@7") (pintype "passive"))
      (node (ref "L4") (pin "1") (pinfunction "1_1") (pintype "passive"))
    )
    (net (code "27") (name "Net-(J3-RX--PadR-@3)") (class "Default")
      (node (ref "J3") (pin "R-@3") (pinfunction "RX-_R-@3") (pintype "passive"))
      (node (ref "J3") (pin "R-@4") (pinfunction "RX-_R-@4") (pintype "passive"))
      (node (ref "L4") (pin "2") (pinfunction "2_2") (pintype "passive"))
    )
    (net (code "28") (name "Net-(J3-TX+-PadT+@13)") (class "Default")
      (node (ref "J3") (pin "T+@13") (pinfunction "TX+_T+@13") (pintype "passive"))
      (node (ref "J3") (pin "T+@14") (pinfunction "TX+_T+@14") (pintype "passive"))
      (node (ref "L1") (pin "1") (pinfunction "1_1") (pintype "passive"))
    )
    (net (code "29") (name "Net-(J3-TX--PadT-@11)") (class "Default")
      (node (ref "J3") (pin "T-@11") (pinfunction "TX-_T-@11") (pintype "passive"))
      (node (ref "J3") (pin "T-@9") (pinfunction "TX-_T-@9") (pintype "passive"))
      (node (ref "L1") (pin "2") (pinfunction "2_2") (pintype "passive"))
    )
    (net (code "30") (name "Net-(L1-Pad3)") (class "Default")
      (node (ref "L1") (pin "3") (pinfunction "3_3") (pintype "passive"))
      (node (ref "T1") (pin "2") (pinfunction "2_2") (pintype "passive"))
    )
    (net (code "31") (name "Net-(L1-Pad4)") (class "Default")
      (node (ref "L1") (pin "4") (pinfunction "4_4") (pintype "passive"))
      (node (ref "T1") (pin "1") (pinfunction "1_1") (pintype "passive"))
    )
    (net (code "32") (name "Net-(L4-Pad3)") (class "Default")
      (node (ref "L4") (pin "3") (pinfunction "3_3") (pintype "passive"))
      (node (ref "T2") (pin "2") (pinfunction "2_2") (pintype "passive"))
    )
    (net (code "33") (name "Net-(L4-Pad4)") (class "Default")
      (node (ref "L4") (pin "4") (pinfunction "4_4") (pintype "passive"))
      (node (ref "T2") (pin "1") (pinfunction "1_1") (pintype "passive"))
    )
    (net (code "34") (name "Net-(LED1-PadC)") (class "Default")
      (node (ref "LED1") (pin "C") (pinfunction "C_C") (pintype "passive"))
      (node (ref "R6") (pin "2") (pinfunction "2_2") (pintype "passive"))
    )
    (net (code "35") (name "Net-(LED2-PadA)") (class "Default")
      (node (ref "LED2") (pin "A") (pinfunction "A_A") (pintype "passive"))
      (node (ref "R40") (pin "2") (pinfunction "2_2") (pintype "passive"))
    )
    (net (code "36") (name "Net-(LED2-PadC)") (class "Default")
      (node (ref "LED2") (pin "C") (pinfunction "C_C") (pintype "passive"))
      (node (ref "U8") (pin "PD11") (pinfunction "PD11_PD11") (pintype "bidirectional"))
    )
    (net (code "37") (name "Net-(LED3-PadA)") (class "Default")
      (node (ref "LED3") (pin "A") (pinfunction "A_A") (pintype "passive"))
      (node (ref "R38") (pin "2") (pinfunction "2_2") (pintype "passive"))
    )
    (net (code "38") (name "Net-(LED3-PadC)") (class "Default")
      (node (ref "LED3") (pin "C") (pinfunction "C_C") (pintype "passive"))
      (node (ref "U8") (pin "PD13") (pinfunction "PD13_PD13") (pintype "bidirectional"))
    )
    (net (code "39") (name "Net-(LED4-PadA)") (class "Default")
      (node (ref "LED4") (pin "A") (pinfunction "A_A") (pintype "passive"))
      (node (ref "R39") (pin "2") (pinfunction "2_2") (pintype "passive"))
    )
    (net (code "40") (name "Net-(LED4-PadC)") (class "Default")
      (node (ref "LED4") (pin "C") (pinfunction "C_C") (pintype "passive"))
      (node (ref "U8") (pin "PD14") (pinfunction "PD14_PD14") (pintype "bidirectional"))
    )
    (net (code "41") (name "Net-(Q1-G)") (class "Default")
      (node (ref "Q1") (pin "1") (pinfunction "G_1") (pintype "passive"))
      (node (ref "R12") (pin "1") (pinfunction "1_1") (pintype "passive"))
      (node (ref "U8") (pin "PE0") (pinfunction "PE0_PE0") (pintype "bidirectional"))
    )
    (net (code "42") (name "Net-(R10-Pad2)") (class "Default")
      (node (ref "R10") (pin "2") (pinfunction "2_2") (pintype "passive"))
      (node (ref "T2") (pin "6") (pinfunction "6_6") (pintype "passive"))
    )
    (net (code "43") (name "Net-(R11-Pad2)") (class "Default")
      (node (ref "R11") (pin "2") (pinfunction "2_2") (pintype "passive"))
      (node (ref "T1") (pin "6") (pinfunction "6_6") (pintype "passive"))
    )
    (net (code "44") (name "Net-(TP1-PadTP)") (class "Default")
      (node (ref "TP1") (pin "TP") (pinfunction "TP_TP") (pintype "input"))
      (node (ref "U8") (pin "BOOT0") (pinfunction "BOOT0_BOOT0") (pintype "bidirectional"))
    )
    (net (code "45") (name "Net-(U3-NINT{slash}TXER{slash}TXD4)") (class "Default")
      (node (ref "R15") (pin "2") (pinfunction "2_2") (pintype "passive"))
      (node (ref "U3") (pin "18") (pinfunction "NINT/TXER/TXD4_18") (pintype "bidirectional"))
    )
    (net (code "46") (name "Net-(U3-RBIAS)") (class "Default")
      (node (ref "R29") (pin "2") (pinfunction "2_2") (pintype "passive"))
      (node (ref "U3") (pin "32") (pinfunction "RBIAS_32") (pintype "input"))
    )
    (net (code "47") (name "Net-(U3-RXN)") (class "Default")
      (node (ref "R22") (pin "1") (pinfunction "1_1") (pintype "passive"))
      (node (ref "T2") (pin "4") (pinfunction "4_4") (pintype "passive"))
      (node (ref "U3") (pin "30") (pinfunction "RXN_30") (pintype "input"))
    )
    (net (code "48") (name "Net-(U3-RXP)") (class "Default")
      (node (ref "R23") (pin "1") (pinfunction "1_1") (pintype "passive"))
      (node (ref "T2") (pin "5") (pinfunction "5_5") (pintype "passive"))
      (node (ref "U3") (pin "31") (pinfunction "RXP_31") (pintype "input"))
    )
    (net (code "49") (name "Net-(U3-TXN)") (class "Default")
      (node (ref "R24") (pin "1") (pinfunction "1_1") (pintype "passive"))
      (node (ref "T1") (pin "4") (pinfunction "4_4") (pintype "passive"))
      (node (ref "U3") (pin "28") (pinfunction "TXN_28") (pintype "output"))
    )
    (net (code "50") (name "Net-(U3-TXP)") (class "Default")
      (node (ref "R25") (pin "1") (pinfunction "1_1") (pintype "passive"))
      (node (ref "T1") (pin "5") (pinfunction "5_5") (pintype "passive"))
      (node (ref "U3") (pin "29") (pinfunction "TXP_29") (pintype "output"))
    )
    (net (code "51") (name "Net-(U3-VDD1A)") (class "Default")
      (node (ref "C23") (pin "2") (pinfunction "2_2") (pintype "passive"))
      (node (ref "C31") (pin "2") (pinfunction "2_2") (pintype "passive"))
      (node (ref "C32") (pin "2") (pinfunction "2_2") (pintype "passive"))
      (node (ref "L3") (pin "1") (pinfunction "1_1") (pintype "passive"))
      (node (ref "R20") (pin "2") (pinfunction "2_2") (pintype "passive"))
      (node (ref "R22") (pin "2") (pinfunction "2_2") (pintype "passive"))
      (node (ref "R23") (pin "2") (pinfunction "2_2") (pintype "passive"))
      (node (ref "R24") (pin "2") (pinfunction "2_2") (pintype "passive"))
      (node (ref "R25") (pin "2") (pinfunction "2_2") (pintype "passive"))
      (node (ref "U3") (pin "1") (pinfunction "VDD2A_1") (pintype "power_in"))
      (node (ref "U3") (pin "27") (pinfunction "VDD1A_27") (pintype "power_in"))
    )
    (net (code "52") (name "Net-(U3-VDDCR)") (class "Default")
      (node (ref "C34") (pin "2") (pinfunction "2_2") (pintype "passive"))
      (node (ref "C53") (pin "2") (pinfunction "2_2") (pintype "passive"))
      (node (ref "U3") (pin "6") (pinfunction "VDDCR_6") (pintype "power_in"))
    )
    (net (code "53") (name "Net-(U10-FB)") (class "Default")
      (node (ref "C26") (pin "2") (pinfunction "2_2") (pintype "passive"))
      (node (ref "R1") (pin "1") (pinfunction "1_1") (pintype "passive"))
      (node (ref "R3") (pin "2") (pinfunction "2_2") (pintype "passive"))
      (node (ref "U10") (pin "6") (pinfunction "FB_6") (pintype "bidirectional"))
    )
    (net (code "54") (name "Net-(U10-RON)") (class "Default")
      (node (ref "R7") (pin "2") (pinfunction "2_2") (pintype "passive"))
      (node (ref "U10") (pin "2") (pinfunction "RON_2") (pintype "bidirectional"))
    )
    (net (code "55") (name "Net-(U10-SS)") (class "Default")
      (node (ref "C21") (pin "1") (pinfunction "1_1") (pintype "passive"))
      (node (ref "U10") (pin "5") (pinfunction "SS_5") (pintype "bidirectional"))
    )
    (net (code "56") (name "Net-(X1-2)") (class "Default")
      (node (ref "C30") (pin "2") (pinfunction "2_2") (pintype "passive"))
      (node (ref "U8") (pin "PH0") (pinfunction "PH0_PH0") (pintype "bidirectional"))
      (node (ref "X1") (pin "3") (pinfunction "2_3") (pintype "passive"))
    )
    (net (code "57") (name "OTG_FS_DM") (class "Default")
      (node (ref "U8") (pin "PA11") (pinfunction "PA11_PA11") (pintype "bidirectional"))
      (node (ref "USB") (pin "P2") (pinfunction "D-_P2") (pintype "bidirectional"))
    )
    (net (code "58") (name "OTG_FS_DP") (class "Default")
      (node (ref "U8") (pin "PA12") (pinfunction "PA12_PA12") (pintype "bidirectional"))
      (node (ref "USB") (pin "P3") (pinfunction "D+_P3") (pintype "bidirectional"))
    )
    (net (code "59") (name "OTG_FS_VBUS") (class "Default")
      (node (ref "D2") (pin "ANODE") (pinfunction "ANODE_ANODE") (pintype "passive"))
      (node (ref "U8") (pin "PA9") (pinfunction "PA9_PA9") (pintype "bidirectional"))
      (node (ref "USB") (pin "P1") (pinfunction "VCC_P1") (pintype "power_in"))
    )
    (net (code "60") (name "PHYAD0") (class "Default")
      (node (ref "R46") (pin "1") (pinfunction "1_1") (pintype "passive"))
      (node (ref "U3") (pin "13") (pinfunction "RXER/RXD4/PHYAD0_13") (pintype "bidirectional"))
    )
    (net (code "61") (name "PHYAD1") (class "Default")
      (node (ref "R47") (pin "1") (pinfunction "1_1") (pintype "passive"))
      (node (ref "U3") (pin "7") (pinfunction "RXCLK/PHYAD1_7") (pintype "bidirectional"))
    )
    (net (code "62") (name "PHYAD2") (class "Default")
      (node (ref "R48") (pin "1") (pinfunction "1_1") (pintype "passive"))
      (node (ref "U3") (pin "8") (pinfunction "RXD3/PHYAD2_8") (pintype "bidirectional"))
    )
    (net (code "63") (name "PHY_CLK_25MHZ") (class "Default")
      (node (ref "U3") (pin "5") (pinfunction "XTAL1/CLKIN_5") (pintype "input"))
      (node (ref "U8") (pin "PA8") (pinfunction "PA8_PA8") (pintype "bidirectional"))
    )
    (net (code "64") (name "RMIISEL") (class "Default")
      (node (ref "R27") (pin "2") (pinfunction "2_2") (pintype "passive"))
      (node (ref "U3") (pin "9") (pinfunction "RXD2/RMIISEL_9") (pintype "bidirectional"))
    )
    (net (code "65") (name "SDIO_CLK") (class "Default")
      (node (ref "SD1") (pin "P5") (pinfunction "5_P5") (pintype "passive"))
      (node (ref "U8") (pin "PC12") (pinfunction "PC12_PC12") (pintype "bidirectional"))
    )
    (net (code "66") (name "SDIO_CMD") (class "Default")
      (node (ref "SD1") (pin "P3") (pinfunction "3_P3") (pintype "passive"))
      (node (ref "U8") (pin "PD2") (pinfunction "PD2_PD2") (pintype "bidirectional"))
    )
    (net (code "67") (name "SDIO_D0") (class "Default")
      (node (ref "SD1") (pin "P7") (pinfunction "7_P7") (pintype "passive"))
      (node (ref "U8") (pin "PC8") (pinfunction "PC8_PC8") (pintype "bidirectional"))
    )
    (net (code "68") (name "SDIO_D1") (class "Default")
      (node (ref "SD1") (pin "P8") (pinfunction "8_P8") (pintype "passive"))
      (node (ref "U8") (pin "PC9") (pinfunction "PC9_PC9") (pintype "bidirectional"))
    )
    (net (code "69") (name "SDIO_D2") (class "Default")
      (node (ref "SD1") (pin "P1") (pinfunction "1_P1") (pintype "passive"))
      (node (ref "U8") (pin "PC10") (pinfunction "PC10_PC10") (pintype "bidirectional"))
    )
    (net (code "70") (name "SDIO_D3") (class "Default")
      (node (ref "SD1") (pin "P2") (pinfunction "2_P2") (pintype "passive"))
      (node (ref "U8") (pin "PC11") (pinfunction "PC11_PC11") (pintype "bidirectional"))
    )
    (net (code "71") (name "VDD") (class "Default")
      (node (ref "C10") (pin "2") (pinfunction "2_2") (pintype "passive"))
      (node (ref "C20") (pin "2") (pinfunction "2_2") (pintype "passive"))
      (node (ref "Q1") (pin "3") (pinfunction "D_3") (pintype "passive"))
      (node (ref "SD1") (pin "P4") (pinfunction "4_P4") (pintype "passive"))
    )
    (net (code "72") (name "VIN") (class "Default")
      (node (ref "C1") (pin "1") (pinfunction "1_1") (pintype "passive"))
      (node (ref "C25") (pin "1") (pinfunction "1_1") (pintype "passive"))
      (node (ref "C33") (pin "1") (pinfunction "1_1") (pintype "passive"))
      (node (ref "D2") (pin "CATHODE") (pinfunction "CATHODE_CATHODE") (pintype "passive"))
      (node (ref "J3") (pin "B+@15") (pinfunction "B+_B+@15") (pintype "power_in"))
      (node (ref "J3") (pin "B+@16") (pinfunction "B+_B+@16") (pintype "power_in"))
      (node (ref "R7") (pin "1") (pinfunction "1_1") (pintype "passive"))
      (node (ref "U10") (pin "1") (pinfunction "VIN_1") (pintype "bidirectional"))
    )
    (net (code "73") (name "unconnected-(U3-CRS-Pad14)") (class "Default")
      (node (ref "U3") (pin "14") (pinfunction "CRS_14") (pintype "output"))
    )
    (net (code "74") (name "unconnected-(U3-LED1{slash}REGOFF-Pad3)") (class "Default")
      (node (ref "U3") (pin "3") (pinfunction "LED1/REGOFF_3") (pintype "bidirectional"))
    )
    (net (code "75") (name "unconnected-(U3-LED2{slash}NINTSEL-Pad2)") (class "Default")
      (node (ref "U3") (pin "2") (pinfunction "LED2/NINTSEL_2") (pintype "bidirectional"))
    )
    (net (code "76") (name "unconnected-(U3-RXDV-Pad26)") (class "Default")
      (node (ref "U3") (pin "26") (pinfunction "RXDV_26") (pintype "output"))
    )
    (net (code "77") (name "unconnected-(U3-TXCLK-Pad20)") (class "Default")
      (node (ref "U3") (pin "20") (pinfunction "TXCLK_20") (pintype "output"))
    )
    (net (code "78") (name "unconnected-(U3-XTAL2-Pad4)") (class "Default")
      (node (ref "U3") (pin "4") (pinfunction "XTAL2_4") (pintype "output"))
    )
    (net (code "79") (name "unconnected-(U8-PadPA0)") (class "Default")
      (node (ref "U8") (pin "PA0") (pinfunction "PA0_PA0") (pintype "bidirectional"))
    )
    (net (code "80") (name "unconnected-(U8-PadPA4)") (class "Default")
      (node (ref "U8") (pin "PA4") (pinfunction "PA4_PA4") (pintype "bidirectional"))
    )
    (net (code "81") (name "unconnected-(U8-PadPA5)") (class "Default")
      (node (ref "U8") (pin "PA5") (pinfunction "PA5_PA5") (pintype "bidirectional"))
    )
    (net (code "82") (name "unconnected-(U8-PadPA6)") (class "Default")
      (node (ref "U8") (pin "PA6") (pinfunction "PA6_PA6") (pintype "bidirectional"))
    )
    (net (code "83") (name "unconnected-(U8-PadPA10)") (class "Default")
      (node (ref "U8") (pin "PA10") (pinfunction "PA10_PA10") (pintype "bidirectional"))
    )
    (net (code "84") (name "unconnected-(U8-PadPB0)") (class "Default")
      (node (ref "U8") (pin "PB0") (pinfunction "PB0_PB0") (pintype "bidirectional"))
    )
    (net (code "85") (name "unconnected-(U8-PadPB1)") (class "Default")
      (node (ref "U8") (pin "PB1") (pinfunction "PB1_PB1") (pintype "bidirectional"))
    )
    (net (code "86") (name "unconnected-(U8-PadPB2)") (class "Default")
      (node (ref "U8") (pin "PB2") (pinfunction "PB2_PB2") (pintype "bidirectional"))
    )
    (net (code "87") (name "unconnected-(U8-PadPB4)") (class "Default")
      (node (ref "U8") (pin "PB4") (pinfunction "PB4_PB4") (pintype "bidirectional"))
    )
    (net (code "88") (name "unconnected-(U8-PadPB5)") (class "Default")
      (node (ref "U8") (pin "PB5") (pinfunction "PB5_PB5") (pintype "bidirectional"))
    )
    (net (code "89") (name "unconnected-(U8-PadPB6)") (class "Default")
      (node (ref "U8") (pin "PB6") (pinfunction "PB6_PB6") (pintype "bidirectional"))
    )
    (net (code "90") (name "unconnected-(U8-PadPB7)") (class "Default")
      (node (ref "U8") (pin "PB7") (pinfunction "PB7_PB7") (pintype "bidirectional"))
    )
    (net (code "91") (name "unconnected-(U8-PadPB8)") (class "Default")
      (node (ref "U8") (pin "PB8") (pinfunction "PB8_PB8") (pintype "bidirectional"))
    )
    (net (code "92") (name "unconnected-(U8-PadPB9)") (class "Default")
      (node (ref "U8") (pin "PB9") (pinfunction "PB9_PB9") (pintype "bidirectional"))
    )
    (net (code "93") (name "unconnected-(U8-PadPB10)") (class "Default")
      (node (ref "U8") (pin "PB10") (pinfunction "PB10_PB10") (pintype "bidirectional"))
    )
    (net (code "94") (name "unconnected-(U8-PadPB14)") (class "Default")
      (node (ref "U8") (pin "PB14") (pinfunction "PB14_PB14") (pintype "bidirectional"))
    )
    (net (code "95") (name "unconnected-(U8-PadPB15)") (class "Default")
      (node (ref "U8") (pin "PB15") (pinfunction "PB15_PB15") (pintype "bidirectional"))
    )
    (net (code "96") (name "unconnected-(U8-PadPC0)") (class "Default")
      (node (ref "U8") (pin "PC0") (pinfunction "PC0_PC0") (pintype "bidirectional"))
    )
    (net (code "97") (name "unconnected-(U8-PadPC2)") (class "Default")
      (node (ref "U8") (pin "PC2") (pinfunction "PC2_PC2") (pintype "bidirectional"))
    )
    (net (code "98") (name "unconnected-(U8-PadPC3)") (class "Default")
      (node (ref "U8") (pin "PC3") (pinfunction "PC3_PC3") (pintype "bidirectional"))
    )
    (net (code "99") (name "unconnected-(U8-PadPC6)") (class "Default")
      (node (ref "U8") (pin "PC6") (pinfunction "PC6_PC6") (pintype "bidirectional"))
    )
    (net (code "100") (name "unconnected-(U8-PadPC7)") (class "Default")
      (node (ref "U8") (pin "PC7") (pinfunction "PC7_PC7") (pintype "bidirectional"))
    )
    (net (code "101") (name "unconnected-(U8-PadPC13)") (class "Default")
      (node (ref "U8") (pin "PC13") (pinfunction "PC13_PC13") (pintype "bidirectional"))
    )
    (net (code "102") (name "unconnected-(U8-PadPC14)") (class "Default")
      (node (ref "U8") (pin "PC14") (pinfunction "PC14_PC14") (pintype "bidirectional"))
    )
    (net (code "103") (name "unconnected-(U8-PadPC15)") (class "Default")
      (node (ref "U8") (pin "PC15") (pinfunction "PC15_PC15") (pintype "bidirectional"))
    )
    (net (code "104") (name "unconnected-(U8-PadPD0)") (class "Default")
      (node (ref "U8") (pin "PD0") (pinfunction "PD0_PD0") (pintype "bidirectional"))
    )
    (net (code "105") (name "unconnected-(U8-PadPD1)") (class "Default")
      (node (ref "U8") (pin "PD1") (pinfunction "PD1_PD1") (pintype "bidirectional"))
    )
    (net (code "106") (name "unconnected-(U8-PadPD3)") (class "Default")
      (node (ref "U8") (pin "PD3") (pinfunction "PD3_PD3") (pintype "bidirectional"))
    )
    (net (code "107") (name "unconnected-(U8-PadPD4)") (class "Default")
      (node (ref "U8") (pin "PD4") (pinfunction "PD4_PD4") (pintype "bidirectional"))
    )
    (net (code "108") (name "unconnected-(U8-PadPD5)") (class "Default")
      (node (ref "U8") (pin "PD5") (pinfunction "PD5_PD5") (pintype "bidirectional"))
    )
    (net (code "109") (name "unconnected-(U8-PadPD6)") (class "Default")
      (node (ref "U8") (pin "PD6") (pinfunction "PD6_PD6") (pintype "bidirectional"))
    )
    (net (code "110") (name "unconnected-(U8-PadPD7)") (class "Default")
      (node (ref "U8") (pin "PD7") (pinfunction "PD7_PD7") (pintype "bidirectional"))
    )
    (net (code "111") (name "unconnected-(U8-PadPD8)") (class "Default")
      (node (ref "U8") (pin "PD8") (pinfunction "PD8_PD8") (pintype "bidirectional"))
    )
    (net (code "112") (name "unconnected-(U8-PadPD9)") (class "Default")
      (node (ref "U8") (pin "PD9") (pinfunction "PD9_PD9") (pintype "bidirectional"))
    )
    (net (code "113") (name "unconnected-(U8-PadPD10)") (class "Default")
      (node (ref "U8") (pin "PD10") (pinfunction "PD10_PD10") (pintype "bidirectional"))
    )
    (net (code "114") (name "unconnected-(U8-PadPD12)") (class "Default")
      (node (ref "U8") (pin "PD12") (pinfunction "PD12_PD12") (pintype "bidirectional"))
    )
    (net (code "115") (name "unconnected-(U8-PadPD15)") (class "Default")
      (node (ref "U8") (pin "PD15") (pinfunction "PD15_PD15") (pintype "bidirectional"))
    )
    (net (code "116") (name "unconnected-(U8-PadPE1)") (class "Default")
      (node (ref "U8") (pin "PE1") (pinfunction "PE1_PE1") (pintype "bidirectional"))
    )
    (net (code "117") (name "unconnected-(U8-PadPE2)") (class "Default")
      (node (ref "U8") (pin "PE2") (pinfunction "PE2_PE2") (pintype "bidirectional"))
    )
    (net (code "118") (name "unconnected-(U8-PadPE3)") (class "Default")
      (node (ref "U8") (pin "PE3") (pinfunction "PE3_PE3") (pintype "bidirectional"))
    )
    (net (code "119") (name "unconnected-(U8-PadPE4)") (class "Default")
      (node (ref "U8") (pin "PE4") (pinfunction "PE4_PE4") (pintype "bidirectional"))
    )
    (net (code "120") (name "unconnected-(U8-PadPE5)") (class "Default")
      (node (ref "U8") (pin "PE5") (pinfunction "PE5_PE5") (pintype "bidirectional"))
    )
    (net (code "121") (name "unconnected-(U8-PadPE6)") (class "Default")
      (node (ref "U8") (pin "PE6") (pinfunction "PE6_PE6") (pintype "bidirectional"))
    )
    (net (code "122") (name "unconnected-(U8-PadPE7)") (class "Default")
      (node (ref "U8") (pin "PE7") (pinfunction "PE7_PE7") (pintype "bidirectional"))
    )
    (net (code "123") (name "unconnected-(U8-PadPE8)") (class "Default")
      (node (ref "U8") (pin "PE8") (pinfunction "PE8_PE8") (pintype "bidirectional"))
    )
    (net (code "124") (name "unconnected-(U8-PadPE9)") (class "Default")
      (node (ref "U8") (pin "PE9") (pinfunction "PE9_PE9") (pintype "bidirectional"))
    )
    (net (code "125") (name "unconnected-(U8-PadPE10)") (class "Default")
      (node (ref "U8") (pin "PE10") (pinfunction "PE10_PE10") (pintype "bidirectional"))
    )
    (net (code "126") (name "unconnected-(U8-PadPE11)") (class "Default")
      (node (ref "U8") (pin "PE11") (pinfunction "PE11_PE11") (pintype "bidirectional"))
    )
    (net (code "127") (name "unconnected-(U8-PadPE12)") (class "Default")
      (node (ref "U8") (pin "PE12") (pinfunction "PE12_PE12") (pintype "bidirectional"))
    )
    (net (code "128") (name "unconnected-(U8-PadPE13)") (class "Default")
      (node (ref "U8") (pin "PE13") (pinfunction "PE13_PE13") (pintype "bidirectional"))
    )
    (net (code "129") (name "unconnected-(U8-PadPE14)") (class "Default")
      (node (ref "U8") (pin "PE14") (pinfunction "PE14_PE14") (pintype "bidirectional"))
    )
    (net (code "130") (name "unconnected-(U8-PadPE15)") (class "Default")
      (node (ref "U8") (pin "PE15") (pinfunction "PE15_PE15") (pintype "bidirectional"))
    )
    (net (code "131") (name "unconnected-(U8-PadVBAT)") (class "Default")
      (node (ref "U8") (pin "VBAT") (pinfunction "VBAT_VBAT") (pintype "bidirectional"))
    )
    (net (code "132") (name "unconnected-(U8-PadVDDA)") (class "Default")
      (node (ref "U8") (pin "VDDA") (pinfunction "VDDA_VDDA") (pintype "bidirectional"))
    )
    (net (code "133") (name "unconnected-(U8-PadVREF+)") (class "Default")
      (node (ref "U8") (pin "VREF+") (pinfunction "VREF+_VREF+") (pintype "bidirectional"))
    )
    (net (code "134") (name "unconnected-(U8-PadVSSA)") (class "Default")
      (node (ref "U8") (pin "VSSA") (pinfunction "VSSA_VSSA") (pintype "bidirectional"))
    )
    (net (code "135") (name "unconnected-(U10-EN-Pad3)") (class "Default")
      (node (ref "U10") (pin "3") (pinfunction "EN_3") (pintype "bidirectional"))
    )
    (net (code "136") (name "unconnected-(USB-ID-PadP4)") (class "Default")
      (node (ref "USB") (pin "P4") (pinfunction "ID_P4") (pintype "bidirectional"))
    )
  )
)
